# Voltage_Board.net
KiCad netlist of a schematic drawn in Altium Designer
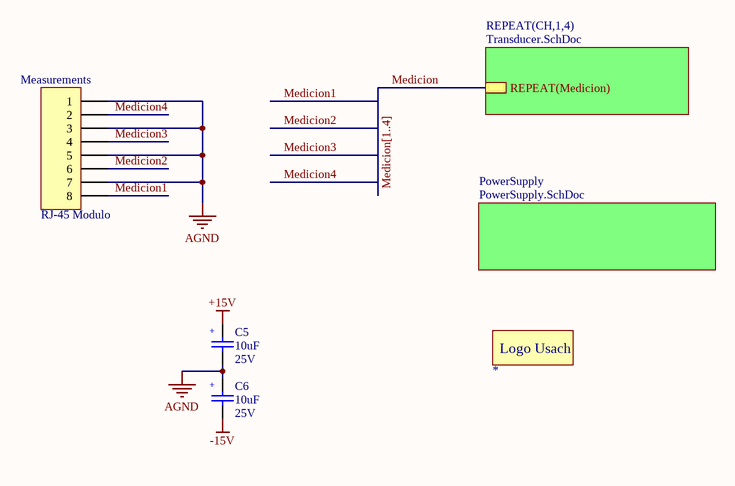
[diagram p0: Voltage_Board.SchDoc]

(export (version "E")
  (design (tool "Eeschema 10.0.6"))
  (components
    (comp (ref "*")
      (value "LOGO USACH")
      (footprint "Logo Usach")
      (libsource (lib "Componentes_SOC") (part "LOGO USACH"))
    )
    (comp (ref "C5")
      (value "10uF")
      (footprint "CAP_1206 Tantalio")
      (description "Capacitor Tantalio")
      (fields (field (name "VOLTAGE") "25V"))
      (libsource (lib "Componentes_SOC") (part "Cap Tantalio 1206"))
    )
    (comp (ref "C6")
      (value "10uF")
      (footprint "CAP_1206 Tantalio")
      (description "Capacitor Tantalio")
      (fields (field (name "VOLTAGE") "25V"))
      (libsource (lib "Componentes_SOC") (part "Cap Tantalio 1206"))
    )
    (comp (ref "Measurements")
      (value "RJ-45 Modulo")
      (footprint "RJ45 1 Modulo SMD")
      (description "Modulo RJ-45 vertical SMD")
      (fields (field (name "PUBLISHER") "Altium Limited"))
      (libsource (lib "Componentes_SOC") (part "RJ45 1 modulo SMD"))
    )
  )
  (nets
    (net (code "1") (name "+15V") (class "Default")
      (node (ref "C5") (pin "1") (pinfunction "1_1") (pintype "passive"))
    )
    (net (code "2") (name "-15V") (class "Default")
      (node (ref "C6") (pin "2") (pinfunction "2_2") (pintype "passive"))
    )
    (net (code "4") (name "/Medicion1") (class "Default")
      (node (ref "Measurements") (pin "8") (pinfunction "8_8") (pintype "passive"))
    )
    (net (code "5") (name "/Medicion2") (class "Default")
      (node (ref "Measurements") (pin "6") (pinfunction "6_6") (pintype "passive"))
    )
    (net (code "6") (name "/Medicion3") (class "Default")
      (node (ref "Measurements") (pin "4") (pinfunction "4_4") (pintype "passive"))
    )
    (net (code "7") (name "/Medicion4") (class "Default")
      (node (ref "Measurements") (pin "2") (pinfunction "2_2") (pintype "passive"))
    )
    (net (code "9") (name "AGND") (class "Default")
      (node (ref "C5") (pin "2") (pinfunction "2_2") (pintype "passive"))
      (node (ref "C6") (pin "1") (pinfunction "1_1") (pintype "passive"))
      (node (ref "Measurements") (pin "1") (pinfunction "1_1") (pintype "passive"))
      (node (ref "Measurements") (pin "3") (pinfunction "3_3") (pintype "passive"))
      (node (ref "Measurements") (pin "5") (pinfunction "5_5") (pintype "passive"))
      (node (ref "Measurements") (pin "7") (pinfunction "7_7") (pintype "passive"))
    )
  )
)
